# Ultra-Mega-PS-Arduino-V1_00.net
KiCad netlist of a schematic drawn in Altium Designer
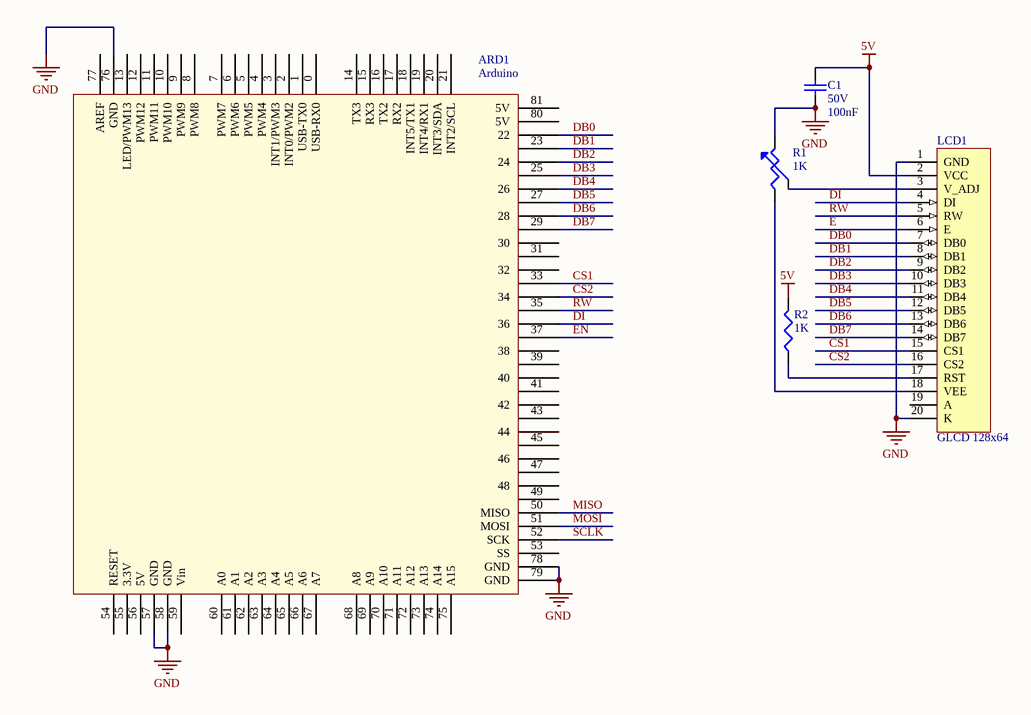
[diagram p0: Ultra-Mega-PS-Arduino-V1.00.SchDoc]

(export (version "E")
  (design (tool "Eeschema 10.0.6"))
  (components
    (comp (ref "ARD1")
      (value "Arduino")
      (footprint "Arduino:Arduino")
      (libsource (lib "Arduino System") (part "Arduino"))
    )
    (comp (ref "C1")
      (value "100nF")
      (footprint "CC0603")
      (description "Capacitor (Semiconductor SIM Model)")
      (fields (field (name "TENSÃO") "50V") (field (name "Comment") "Capacitor Cerâmico"))
      (libsource (lib "NavarroCAP") (part "Cap 100nF 50V 0603 X7R"))
    )
    (comp (ref "LCD1")
      (value "GLCD 128x64")
      (footprint "LCD-128x64")
      (description "GLCD 128x64 SSC12A64DLYY")
      (libsource (lib "Navarro") (part "LCD12864"))
    )
    (comp (ref "R1")
      (value "1K")
      (footprint "POT")
      (description "Trimmer")
      (fields (field (name "Comment") "Potenciômetro"))
      (libsource (lib "NavarroRES") (part "Res Trim"))
    )
    (comp (ref "R2")
      (value "1K")
      (footprint "CC0603")
      (description "Resistor")
      (libsource (lib "NavarroRES") (part "Res 1K 1% 0603 1/10W"))
    )
  )
  (nets
    (net (code "1") (name "/CS1") (class "Default")
      (node (ref "ARD1") (pin "33") (pinfunction "33_33") (pintype "passive"))
      (node (ref "LCD1") (pin "15") (pinfunction "CS1_15") (pintype "passive"))
    )
    (net (code "2") (name "/CS2") (class "Default")
      (node (ref "ARD1") (pin "34") (pinfunction "34_34") (pintype "passive"))
      (node (ref "LCD1") (pin "16") (pinfunction "CS2_16") (pintype "passive"))
    )
    (net (code "3") (name "/DB0") (class "Default")
      (node (ref "ARD1") (pin "22") (pinfunction "22_22") (pintype "passive"))
      (node (ref "LCD1") (pin "7") (pinfunction "DB0_7") (pintype "bidirectional"))
    )
    (net (code "4") (name "/DB1") (class "Default")
      (node (ref "ARD1") (pin "23") (pinfunction "23_23") (pintype "passive"))
      (node (ref "LCD1") (pin "8") (pinfunction "DB1_8") (pintype "bidirectional"))
    )
    (net (code "5") (name "/DB2") (class "Default")
      (node (ref "ARD1") (pin "24") (pinfunction "24_24") (pintype "passive"))
      (node (ref "LCD1") (pin "9") (pinfunction "DB2_9") (pintype "bidirectional"))
    )
    (net (code "6") (name "/DB3") (class "Default")
      (node (ref "ARD1") (pin "25") (pinfunction "25_25") (pintype "passive"))
      (node (ref "LCD1") (pin "10") (pinfunction "DB3_10") (pintype "bidirectional"))
    )
    (net (code "7") (name "/DB4") (class "Default")
      (node (ref "ARD1") (pin "26") (pinfunction "26_26") (pintype "passive"))
      (node (ref "LCD1") (pin "11") (pinfunction "DB4_11") (pintype "bidirectional"))
    )
    (net (code "8") (name "/DB5") (class "Default")
      (node (ref "ARD1") (pin "27") (pinfunction "27_27") (pintype "passive"))
      (node (ref "LCD1") (pin "12") (pinfunction "DB5_12") (pintype "bidirectional"))
    )
    (net (code "9") (name "/DB6") (class "Default")
      (node (ref "ARD1") (pin "28") (pinfunction "28_28") (pintype "passive"))
      (node (ref "LCD1") (pin "13") (pinfunction "DB6_13") (pintype "bidirectional"))
    )
    (net (code "10") (name "/DB7") (class "Default")
      (node (ref "ARD1") (pin "29") (pinfunction "29_29") (pintype "passive"))
      (node (ref "LCD1") (pin "14") (pinfunction "DB7_14") (pintype "bidirectional"))
    )
    (net (code "11") (name "/DI") (class "Default")
      (node (ref "ARD1") (pin "36") (pinfunction "36_36") (pintype "passive"))
      (node (ref "LCD1") (pin "4") (pinfunction "DI_4") (pintype "input"))
    )
    (net (code "12") (name "/E") (class "Default")
      (node (ref "LCD1") (pin "6") (pinfunction "E_6") (pintype "input"))
    )
    (net (code "13") (name "/EN") (class "Default")
      (node (ref "ARD1") (pin "37") (pinfunction "37_37") (pintype "passive"))
    )
    (net (code "14") (name "/MISO") (class "Default")
      (node (ref "ARD1") (pin "50") (pinfunction "MISO_50") (pintype "passive"))
    )
    (net (code "15") (name "/MOSI") (class "Default")
      (node (ref "ARD1") (pin "51") (pinfunction "MOSI_51") (pintype "passive"))
    )
    (net (code "16") (name "/RW") (class "Default")
      (node (ref "ARD1") (pin "35") (pinfunction "35_35") (pintype "passive"))
      (node (ref "LCD1") (pin "5") (pinfunction "RW_5") (pintype "input"))
    )
    (net (code "17") (name "/SCLK") (class "Default")
      (node (ref "ARD1") (pin "52") (pinfunction "SCK_52") (pintype "passive"))
    )
    (net (code "18") (name "5V") (class "Default")
      (node (ref "C1") (pin "2") (pinfunction "2_2") (pintype "passive"))
      (node (ref "LCD1") (pin "2") (pinfunction "VCC_2") (pintype "power_in"))
      (node (ref "R2") (pin "2") (pinfunction "2_2") (pintype "passive"))
    )
    (net (code "19") (name "GND") (class "Default")
      (node (ref "ARD1") (pin "57") (pinfunction "GND_57") (pintype "passive"))
      (node (ref "ARD1") (pin "58") (pinfunction "GND_58") (pintype "passive"))
      (node (ref "ARD1") (pin "76") (pinfunction "GND_76") (pintype "passive"))
      (node (ref "ARD1") (pin "78") (pinfunction "GND_78") (pintype "passive"))
      (node (ref "ARD1") (pin "79") (pinfunction "GND_79") (pintype "passive"))
      (node (ref "C1") (pin "1") (pinfunction "1_1") (pintype "passive"))
      (node (ref "LCD1") (pin "1") (pinfunction "GND_1") (pintype "power_in"))
      (node (ref "LCD1") (pin "20") (pinfunction "K_20") (pintype "passive"))
      (node (ref "R1") (pin "1") (pinfunction "1_1") (pintype "passive"))
    )
    (net (code "20") (name "Net-(LCD1-RST)") (class "Default")
      (node (ref "LCD1") (pin "17") (pinfunction "RST_17") (pintype "passive"))
      (node (ref "R2") (pin "1") (pinfunction "1_1") (pintype "passive"))
    )
    (net (code "21") (name "Net-(LCD1-VEE)") (class "Default")
      (node (ref "LCD1") (pin "18") (pinfunction "VEE_18") (pintype "passive"))
      (node (ref "R1") (pin "2") (pinfunction "2_2") (pintype "passive"))
    )
    (net (code "22") (name "Net-(LCD1-V_ADJ)") (class "Default")
      (node (ref "LCD1") (pin "3") (pinfunction "V_ADJ_3") (pintype "power_in"))
      (node (ref "R1") (pin "3") (pinfunction "TAP_3") (pintype "passive"))
    )
    (net (code "23") (name "unconnected-(ARD1-3.3V-Pad55)") (class "Default")
      (node (ref "ARD1") (pin "55") (pinfunction "3.3V_55") (pintype "passive"))
    )
    (net (code "24") (name "unconnected-(ARD1-5V-Pad56)") (class "Default")
      (node (ref "ARD1") (pin "56") (pinfunction "5V_56") (pintype "passive"))
    )
    (net (code "25") (name "unconnected-(ARD1-5V-Pad80)") (class "Default")
      (node (ref "ARD1") (pin "80") (pinfunction "5V_80") (pintype "passive"))
    )
    (net (code "26") (name "unconnected-(ARD1-5V-Pad81)") (class "Default")
      (node (ref "ARD1") (pin "81") (pinfunction "5V_81") (pintype "passive"))
    )
    (net (code "27") (name "unconnected-(ARD1-A0-Pad60)") (class "Default")
      (node (ref "ARD1") (pin "60") (pinfunction "A0_60") (pintype "passive"))
    )
    (net (code "28") (name "unconnected-(ARD1-A1-Pad61)") (class "Default")
      (node (ref "ARD1") (pin "61") (pinfunction "A1_61") (pintype "passive"))
    )
    (net (code "29") (name "unconnected-(ARD1-A2-Pad62)") (class "Default")
      (node (ref "ARD1") (pin "62") (pinfunction "A2_62") (pintype "passive"))
    )
    (net (code "30") (name "unconnected-(ARD1-A3-Pad63)") (class "Default")
      (node (ref "ARD1") (pin "63") (pinfunction "A3_63") (pintype "passive"))
    )
    (net (code "31") (name "unconnected-(ARD1-A4-Pad64)") (class "Default")
      (node (ref "ARD1") (pin "64") (pinfunction "A4_64") (pintype "passive"))
    )
    (net (code "32") (name "unconnected-(ARD1-A5-Pad65)") (class "Default")
      (node (ref "ARD1") (pin "65") (pinfunction "A5_65") (pintype "passive"))
    )
    (net (code "33") (name "unconnected-(ARD1-A6-Pad66)") (class "Default")
      (node (ref "ARD1") (pin "66") (pinfunction "A6_66") (pintype "passive"))
    )
    (net (code "34") (name "unconnected-(ARD1-A7-Pad67)") (class "Default")
      (node (ref "ARD1") (pin "67") (pinfunction "A7_67") (pintype "passive"))
    )
    (net (code "35") (name "unconnected-(ARD1-A8-Pad68)") (class "Default")
      (node (ref "ARD1") (pin "68") (pinfunction "A8_68") (pintype "passive"))
    )
    (net (code "36") (name "unconnected-(ARD1-A9-Pad69)") (class "Default")
      (node (ref "ARD1") (pin "69") (pinfunction "A9_69") (pintype "passive"))
    )
    (net (code "37") (name "unconnected-(ARD1-A10-Pad70)") (class "Default")
      (node (ref "ARD1") (pin "70") (pinfunction "A10_70") (pintype "passive"))
    )
    (net (code "38") (name "unconnected-(ARD1-A11-Pad71)") (class "Default")
      (node (ref "ARD1") (pin "71") (pinfunction "A11_71") (pintype "passive"))
    )
    (net (code "39") (name "unconnected-(ARD1-A12-Pad72)") (class "Default")
      (node (ref "ARD1") (pin "72") (pinfunction "A12_72") (pintype "passive"))
    )
    (net (code "40") (name "unconnected-(ARD1-A13-Pad73)") (class "Default")
      (node (ref "ARD1") (pin "73") (pinfunction "A13_73") (pintype "passive"))
    )
    (net (code "41") (name "unconnected-(ARD1-A14-Pad74)") (class "Default")
      (node (ref "ARD1") (pin "74") (pinfunction "A14_74") (pintype "passive"))
    )
    (net (code "42") (name "unconnected-(ARD1-A15-Pad75)") (class "Default")
      (node (ref "ARD1") (pin "75") (pinfunction "A15_75") (pintype "passive"))
    )
    (net (code "43") (name "unconnected-(ARD1-AREF-Pad77)") (class "Default")
      (node (ref "ARD1") (pin "77") (pinfunction "AREF_77") (pintype "passive"))
    )
    (net (code "44") (name "unconnected-(ARD1-INT0{slash}PWM2-Pad2)") (class "Default")
      (node (ref "ARD1") (pin "2") (pinfunction "INT0/PWM2_2") (pintype "passive"))
    )
    (net (code "45") (name "unconnected-(ARD1-INT1{slash}PWM3-Pad3)") (class "Default")
      (node (ref "ARD1") (pin "3") (pinfunction "INT1/PWM3_3") (pintype "passive"))
    )
    (net (code "46") (name "unconnected-(ARD1-INT2{slash}SCL-Pad21)") (class "Default")
      (node (ref "ARD1") (pin "21") (pinfunction "INT2/SCL_21") (pintype "passive"))
    )
    (net (code "47") (name "unconnected-(ARD1-INT3{slash}SDA-Pad20)") (class "Default")
      (node (ref "ARD1") (pin "20") (pinfunction "INT3/SDA_20") (pintype "passive"))
    )
    (net (code "48") (name "unconnected-(ARD1-INT4{slash}RX1-Pad19)") (class "Default")
      (node (ref "ARD1") (pin "19") (pinfunction "INT4/RX1_19") (pintype "passive"))
    )
    (net (code "49") (name "unconnected-(ARD1-INT5{slash}TX1-Pad18)") (class "Default")
      (node (ref "ARD1") (pin "18") (pinfunction "INT5/TX1_18") (pintype "passive"))
    )
    (net (code "50") (name "unconnected-(ARD1-LED{slash}PWM13-Pad13)") (class "Default")
      (node (ref "ARD1") (pin "13") (pinfunction "LED/PWM13_13") (pintype "passive"))
    )
    (net (code "51") (name "unconnected-(ARD1-PWM4-Pad4)") (class "Default")
      (node (ref "ARD1") (pin "4") (pinfunction "PWM4_4") (pintype "passive"))
    )
    (net (code "52") (name "unconnected-(ARD1-PWM5-Pad5)") (class "Default")
      (node (ref "ARD1") (pin "5") (pinfunction "PWM5_5") (pintype "passive"))
    )
    (net (code "53") (name "unconnected-(ARD1-PWM6-Pad6)") (class "Default")
      (node (ref "ARD1") (pin "6") (pinfunction "PWM6_6") (pintype "passive"))
    )
    (net (code "54") (name "unconnected-(ARD1-PWM7-Pad7)") (class "Default")
      (node (ref "ARD1") (pin "7") (pinfunction "PWM7_7") (pintype "passive"))
    )
    (net (code "55") (name "unconnected-(ARD1-PWM8-Pad8)") (class "Default")
      (node (ref "ARD1") (pin "8") (pinfunction "PWM8_8") (pintype "passive"))
    )
    (net (code "56") (name "unconnected-(ARD1-PWM9-Pad9)") (class "Default")
      (node (ref "ARD1") (pin "9") (pinfunction "PWM9_9") (pintype "passive"))
    )
    (net (code "57") (name "unconnected-(ARD1-PWM10-Pad10)") (class "Default")
      (node (ref "ARD1") (pin "10") (pinfunction "PWM10_10") (pintype "passive"))
    )
    (net (code "58") (name "unconnected-(ARD1-PWM11-Pad11)") (class "Default")
      (node (ref "ARD1") (pin "11") (pinfunction "PWM11_11") (pintype "passive"))
    )
    (net (code "59") (name "unconnected-(ARD1-PWM12-Pad12)") (class "Default")
      (node (ref "ARD1") (pin "12") (pinfunction "PWM12_12") (pintype "passive"))
    )
    (net (code "60") (name "unconnected-(ARD1-Pad30)") (class "Default")
      (node (ref "ARD1") (pin "30") (pinfunction "30_30") (pintype "passive"))
    )
    (net (code "61") (name "unconnected-(ARD1-Pad31)") (class "Default")
      (node (ref "ARD1") (pin "31") (pinfunction "31_31") (pintype "passive"))
    )
    (net (code "62") (name "unconnected-(ARD1-Pad32)") (class "Default")
      (node (ref "ARD1") (pin "32") (pinfunction "32_32") (pintype "passive"))
    )
    (net (code "63") (name "unconnected-(ARD1-Pad38)") (class "Default")
      (node (ref "ARD1") (pin "38") (pinfunction "38_38") (pintype "passive"))
    )
    (net (code "64") (name "unconnected-(ARD1-Pad39)") (class "Default")
      (node (ref "ARD1") (pin "39") (pinfunction "39_39") (pintype "passive"))
    )
    (net (code "65") (name "unconnected-(ARD1-Pad40)") (class "Default")
      (node (ref "ARD1") (pin "40") (pinfunction "40_40") (pintype "passive"))
    )
    (net (code "66") (name "unconnected-(ARD1-Pad41)") (class "Default")
      (node (ref "ARD1") (pin "41") (pinfunction "41_41") (pintype "passive"))
    )
    (net (code "67") (name "unconnected-(ARD1-Pad42)") (class "Default")
      (node (ref "ARD1") (pin "42") (pinfunction "42_42") (pintype "passive"))
    )
    (net (code "68") (name "unconnected-(ARD1-Pad43)") (class "Default")
      (node (ref "ARD1") (pin "43") (pinfunction "43_43") (pintype "passive"))
    )
    (net (code "69") (name "unconnected-(ARD1-Pad44)") (class "Default")
      (node (ref "ARD1") (pin "44") (pinfunction "44_44") (pintype "passive"))
    )
    (net (code "70") (name "unconnected-(ARD1-Pad45)") (class "Default")
      (node (ref "ARD1") (pin "45") (pinfunction "45_45") (pintype "passive"))
    )
    (net (code "71") (name "unconnected-(ARD1-Pad46)") (class "Default")
      (node (ref "ARD1") (pin "46") (pinfunction "46_46") (pintype "passive"))
    )
    (net (code "72") (name "unconnected-(ARD1-Pad47)") (class "Default")
      (node (ref "ARD1") (pin "47") (pinfunction "47_47") (pintype "passive"))
    )
    (net (code "73") (name "unconnected-(ARD1-Pad48)") (class "Default")
      (node (ref "ARD1") (pin "48") (pinfunction "48_48") (pintype "passive"))
    )
    (net (code "74") (name "unconnected-(ARD1-Pad49)") (class "Default")
      (node (ref "ARD1") (pin "49") (pinfunction "49_49") (pintype "passive"))
    )
    (net (code "75") (name "unconnected-(ARD1-RESET-Pad54)") (class "Default")
      (node (ref "ARD1") (pin "54") (pinfunction "RESET_54") (pintype "passive"))
    )
    (net (code "76") (name "unconnected-(ARD1-RX2-Pad17)") (class "Default")
      (node (ref "ARD1") (pin "17") (pinfunction "RX2_17") (pintype "passive"))
    )
    (net (code "77") (name "unconnected-(ARD1-RX3-Pad15)") (class "Default")
      (node (ref "ARD1") (pin "15") (pinfunction "RX3_15") (pintype "passive"))
    )
    (net (code "78") (name "unconnected-(ARD1-SS-Pad53)") (class "Default")
      (node (ref "ARD1") (pin "53") (pinfunction "SS_53") (pintype "passive"))
    )
    (net (code "79") (name "unconnected-(ARD1-TX2-Pad16)") (class "Default")
      (node (ref "ARD1") (pin "16") (pinfunction "TX2_16") (pintype "passive"))
    )
    (net (code "80") (name "unconnected-(ARD1-TX3-Pad14)") (class "Default")
      (node (ref "ARD1") (pin "14") (pinfunction "TX3_14") (pintype "passive"))
    )
    (net (code "81") (name "unconnected-(ARD1-USB-RX0-Pad0)") (class "Default")
      (node (ref "ARD1") (pin "0") (pinfunction "USB-RX0_0") (pintype "passive"))
    )
    (net (code "82") (name "unconnected-(ARD1-USB-TX0-Pad1)") (class "Default")
      (node (ref "ARD1") (pin "1") (pinfunction "USB-TX0_1") (pintype "passive"))
    )
    (net (code "83") (name "unconnected-(ARD1-Vin-Pad59)") (class "Default")
      (node (ref "ARD1") (pin "59") (pinfunction "Vin_59") (pintype "passive"))
    )
    (net (code "84") (name "unconnected-(LCD1-A-Pad19)") (class "Default")
      (node (ref "LCD1") (pin "19") (pinfunction "A_19") (pintype "passive"))
    )
  )
)
